# SCC.net
KiCad netlist of a schematic drawn in EAGLE
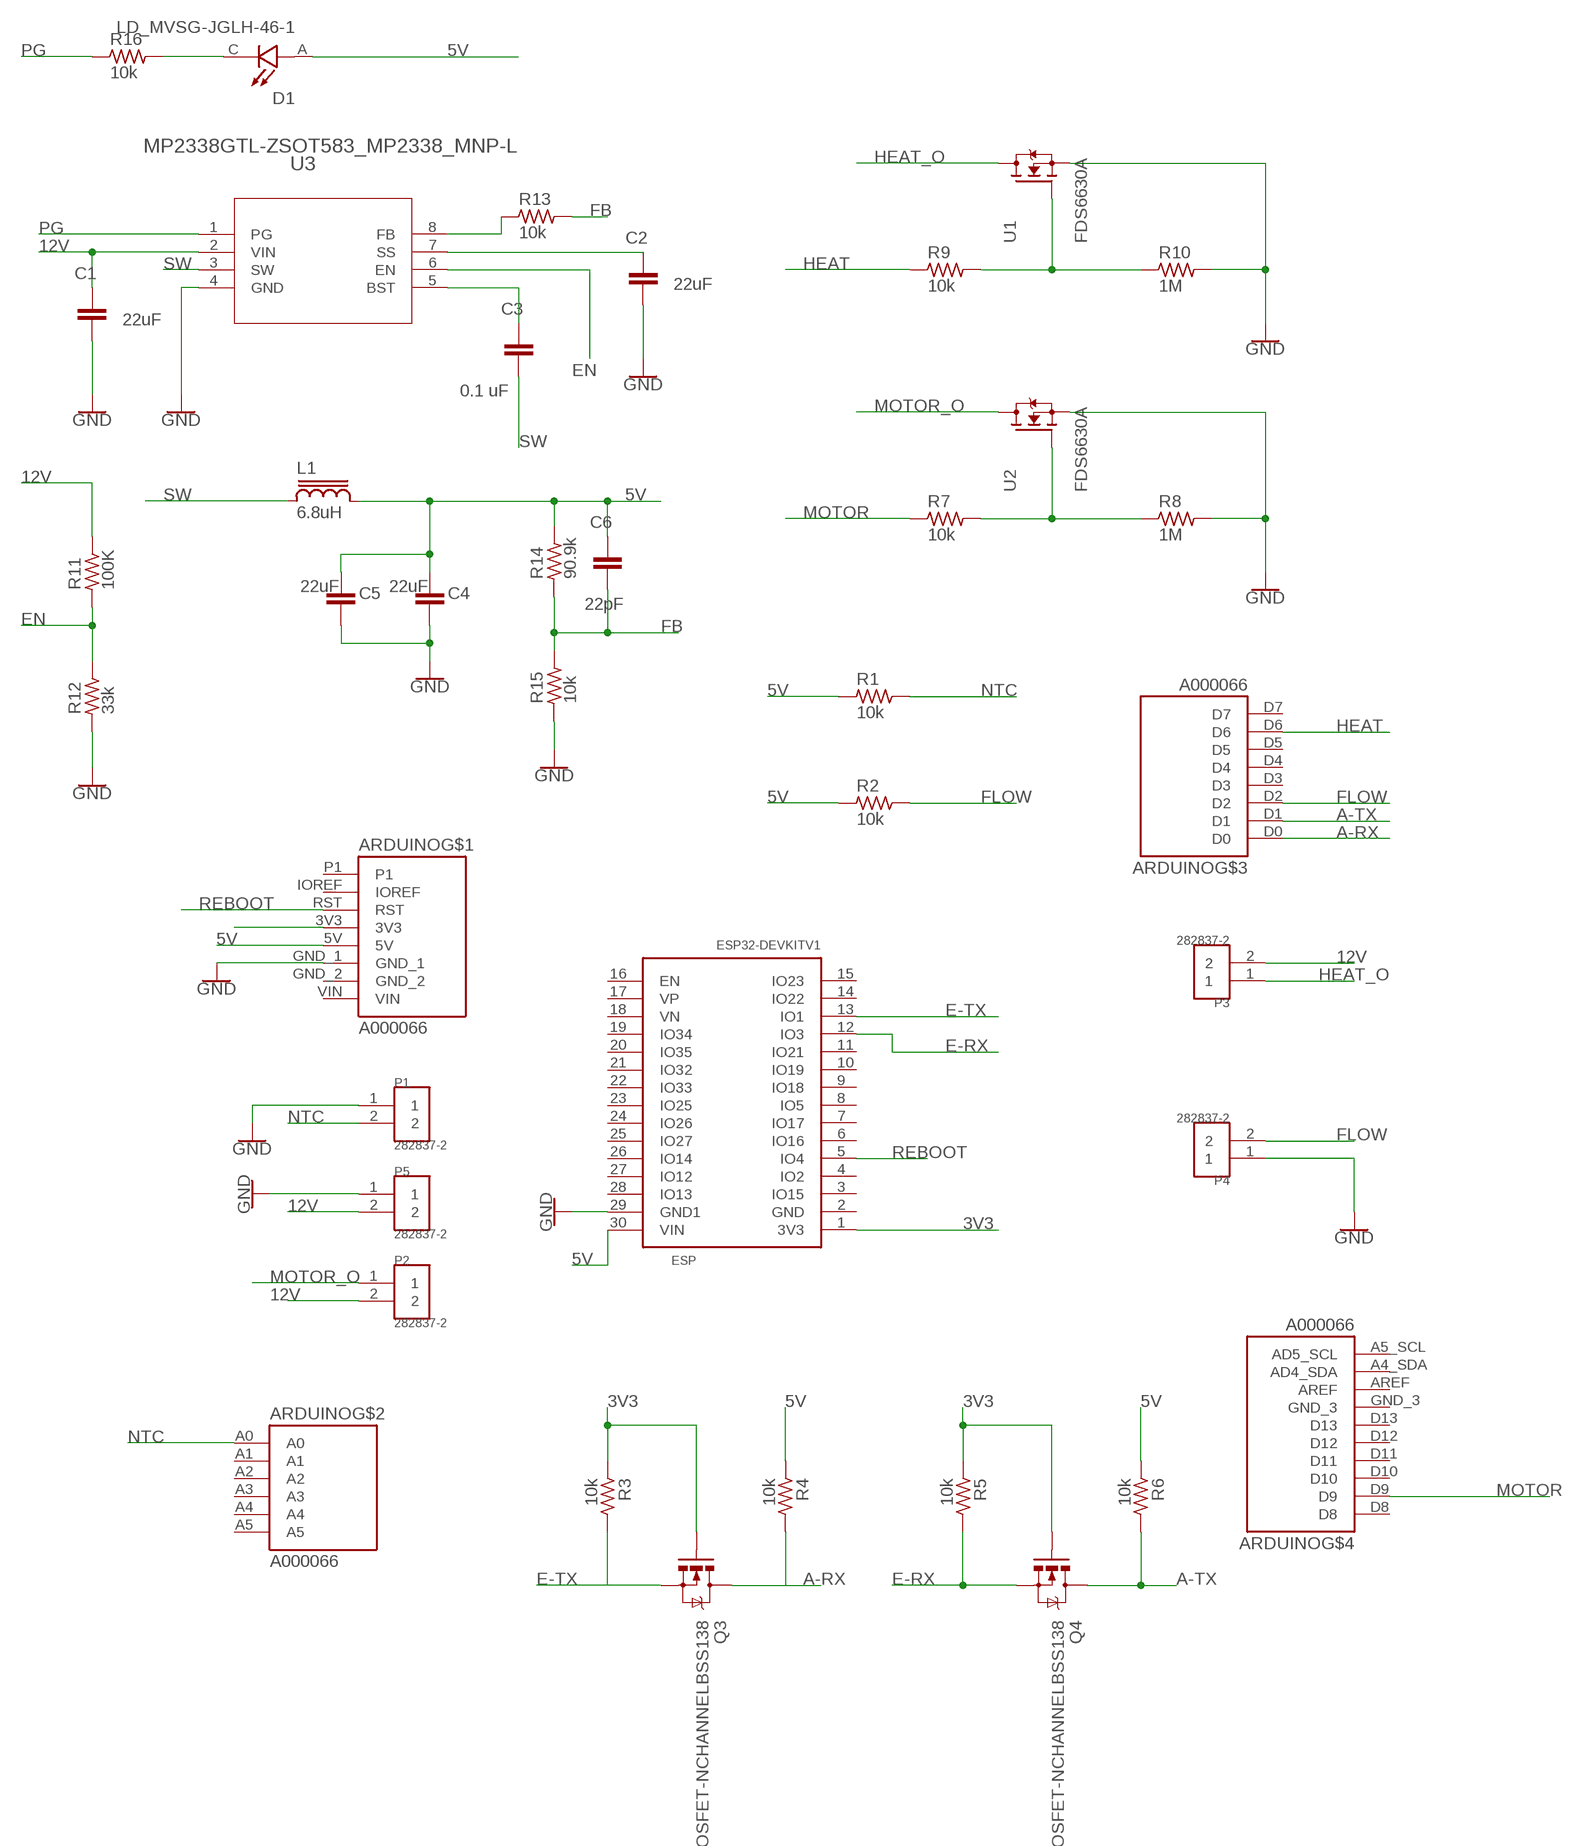
[diagram p0: schematic, sheet 1]

(export (version "E")
  (design (tool "Eeschema 10.0.6"))
  (components
    (comp (ref "ARDUINO")
      (value "A000066")
      (footprint "eagle-import:ARDUINO_A000066")
      (fields (field (name "MF") "Arduino"))
      (libsource (lib "eagle-import") (part "A000066"))
    )
    (comp (ref "C1")
      (value "22uF")
      (footprint "eagle-import:CAP_1206")
      (fields
        (field (name "DIGIKEY_PART_NUMBER") "GRM31CR60J107ME39L")
        (field (name "MANUFACTURER") "Murata Electronics North America")
        (field (name "CREATED_BY") "PCBLayout.com")
      )
      (libsource (lib "eagle-import") (part "GRM31CR60J107ME39L"))
    )
    (comp (ref "C2")
      (value "22uF")
      (footprint "eagle-import:CAP_1206")
      (fields
        (field (name "DIGIKEY_PART_NUMBER") "GRM31CR60J107ME39L")
        (field (name "MANUFACTURER") "Murata Electronics North America")
        (field (name "CREATED_BY") "PCBLayout.com")
      )
      (libsource (lib "eagle-import") (part "GRM31CR60J107ME39L"))
    )
    (comp (ref "C3")
      (value "0.1 uF")
      (footprint "eagle-import:CAP_0805")
      (fields
        (field (name "DIGIKEY_PART_NUMBER") "311-1140-2-ND")
        (field (name "MANUFACTURER") "Yageo")
        (field (name "MPN") "CC0805KRX7R9BB104")
        (field (name "CREATED_BY") "PCBLayout.com")
      )
      (libsource (lib "eagle-import") (part "CC0805KRX7R9BB104"))
    )
    (comp (ref "C4")
      (value "22uF")
      (footprint "eagle-import:CAP_1206")
      (fields
        (field (name "DIGIKEY_PART_NUMBER") "GRM31CR60J107ME39L")
        (field (name "MANUFACTURER") "Murata Electronics North America")
        (field (name "CREATED_BY") "PCBLayout.com")
      )
      (libsource (lib "eagle-import") (part "GRM31CR60J107ME39L"))
    )
    (comp (ref "C5")
      (value "22uF")
      (footprint "eagle-import:CAP_1206")
      (fields
        (field (name "DIGIKEY_PART_NUMBER") "GRM31CR60J107ME39L")
        (field (name "MANUFACTURER") "Murata Electronics North America")
        (field (name "CREATED_BY") "PCBLayout.com")
      )
      (libsource (lib "eagle-import") (part "GRM31CR60J107ME39L"))
    )
    (comp (ref "C6")
      (value "22pF")
      (footprint "eagle-import:CAP_0805")
      (fields
        (field (name "DIGIKEY_PART_NUMBER") "311-1140-2-ND")
        (field (name "MANUFACTURER") "Yageo")
        (field (name "MPN") "CC0805KRX7R9BB104")
        (field (name "CREATED_BY") "PCBLayout.com")
      )
      (libsource (lib "eagle-import") (part "CC0805KRX7R9BB104"))
    )
    (comp (ref "D1")
      (value "LD_MVSG-JGLH-46-1")
      (footprint "eagle-import:LED_LD_MVSG-JGLH-46-1")
      (fields (field (name "MF") "OSRAM Opto") (field (name "MP") "LCW MVSG.EC-AZBZ-4R9T-1"))
      (libsource (lib "eagle-import") (part "LD_MVSG-JGLH-46-1"))
    )
    (comp (ref "ESP")
      (value "ESP32DEVKITV1")
      (footprint "eagle-import:ESP32-DEVKITV1")
      (libsource (lib "eagle-import") (part "ESP32DEVKITV1"))
    )
    (comp (ref "L1")
      (value "6.8uH")
      (footprint "eagle-import:INDUCTOR-BOURNS_SRN8040")
      (libsource (lib "eagle-import") (part "INDUCTOR-BOURNS_SRN8040"))
    )
    (comp (ref "P1")
      (value "282837-2")
      (footprint "eagle-import:TE_282837-2")
      (fields (field (name "MF") "On Shore") (field (name "MP") "OSTTE020104"))
      (libsource (lib "eagle-import") (part "282837-2"))
    )
    (comp (ref "P2")
      (value "282837-2")
      (footprint "eagle-import:TE_282837-2")
      (fields (field (name "MF") "On Shore") (field (name "MP") "OSTTE020104"))
      (libsource (lib "eagle-import") (part "282837-2"))
    )
    (comp (ref "P3")
      (value "282837-2")
      (footprint "eagle-import:TE_282837-2")
      (fields (field (name "MF") "On Shore") (field (name "MP") "OSTTE020104"))
      (libsource (lib "eagle-import") (part "282837-2"))
    )
    (comp (ref "P4")
      (value "282837-2")
      (footprint "eagle-import:TE_282837-2")
      (fields (field (name "MF") "On Shore") (field (name "MP") "OSTTE020104"))
      (libsource (lib "eagle-import") (part "282837-2"))
    )
    (comp (ref "P5")
      (value "282837-2")
      (footprint "eagle-import:TE_282837-2")
      (fields (field (name "MF") "On Shore") (field (name "MP") "OSTTE020104"))
      (libsource (lib "eagle-import") (part "282837-2"))
    )
    (comp (ref "Q3")
      (value "MOSFET-NCHANNELBSS138")
      (footprint "eagle-import:SOT23")
      (libsource (lib "eagle-import") (part "MOSFET-NCHANNELBSS138"))
    )
    (comp (ref "Q4")
      (value "MOSFET-NCHANNELBSS138")
      (footprint "eagle-import:SOT23")
      (libsource (lib "eagle-import") (part "MOSFET-NCHANNELBSS138"))
    )
    (comp (ref "R1")
      (value "10k")
      (footprint "eagle-import:RC-MASTER-SMD_R0603MP")
      (libsource (lib "eagle-import") (part "RC-MASTER-SMD_R_0603MP"))
    )
    (comp (ref "R2")
      (value "10k")
      (footprint "eagle-import:RC-MASTER-SMD_R0603MP")
      (libsource (lib "eagle-import") (part "RC-MASTER-SMD_R_0603MP"))
    )
    (comp (ref "R3")
      (value "10k")
      (footprint "eagle-import:RC-MASTER-SMD_R0603MP")
      (libsource (lib "eagle-import") (part "RC-MASTER-SMD_R_0603MP"))
    )
    (comp (ref "R4")
      (value "10k")
      (footprint "eagle-import:RC-MASTER-SMD_R0603MP")
      (libsource (lib "eagle-import") (part "RC-MASTER-SMD_R_0603MP"))
    )
    (comp (ref "R5")
      (value "10k")
      (footprint "eagle-import:RC-MASTER-SMD_R0603MP")
      (libsource (lib "eagle-import") (part "RC-MASTER-SMD_R_0603MP"))
    )
    (comp (ref "R6")
      (value "10k")
      (footprint "eagle-import:RC-MASTER-SMD_R0603MP")
      (libsource (lib "eagle-import") (part "RC-MASTER-SMD_R_0603MP"))
    )
    (comp (ref "R7")
      (value "10k")
      (footprint "eagle-import:RC-MASTER-SMD_R0603MP")
      (libsource (lib "eagle-import") (part "RC-MASTER-SMD_R_0603MP"))
    )
    (comp (ref "R8")
      (value "1M")
      (footprint "eagle-import:RC-MASTER-SMD_R0603MP")
      (libsource (lib "eagle-import") (part "RC-MASTER-SMD_R_0603MP"))
    )
    (comp (ref "R9")
      (value "10k")
      (footprint "eagle-import:RC-MASTER-SMD_R0603MP")
      (libsource (lib "eagle-import") (part "RC-MASTER-SMD_R_0603MP"))
    )
    (comp (ref "R10")
      (value "1M")
      (footprint "eagle-import:RC-MASTER-SMD_R0603MP")
      (libsource (lib "eagle-import") (part "RC-MASTER-SMD_R_0603MP"))
    )
    (comp (ref "R11")
      (value "100K")
      (footprint "eagle-import:RC-MASTER-SMD_R0603MP")
      (libsource (lib "eagle-import") (part "RC-MASTER-SMD_R_0603MP"))
    )
    (comp (ref "R12")
      (value "33k")
      (footprint "eagle-import:RC-MASTER-SMD_R0603MP")
      (libsource (lib "eagle-import") (part "RC-MASTER-SMD_R_0603MP"))
    )
    (comp (ref "R13")
      (value "10k")
      (footprint "eagle-import:RC-MASTER-SMD_R0603MP")
      (libsource (lib "eagle-import") (part "RC-MASTER-SMD_R_0603MP"))
    )
    (comp (ref "R14")
      (value "90.9k")
      (footprint "eagle-import:RC-MASTER-SMD_R0603MP")
      (libsource (lib "eagle-import") (part "RC-MASTER-SMD_R_0603MP"))
    )
    (comp (ref "R15")
      (value "10k")
      (footprint "eagle-import:RC-MASTER-SMD_R0603MP")
      (libsource (lib "eagle-import") (part "RC-MASTER-SMD_R_0603MP"))
    )
    (comp (ref "R16")
      (value "10k")
      (footprint "eagle-import:RC-MASTER-SMD_R0603MP")
      (libsource (lib "eagle-import") (part "RC-MASTER-SMD_R_0603MP"))
    )
    (comp (ref "U1")
      (value "FDS6630A")
      (footprint "eagle-import:SOIC127P600X175-8N")
      (fields (field (name "MANUFACTURER") "ON SEMICONDUCTOR"))
      (libsource (lib "eagle-import") (part "FDS6630A"))
    )
    (comp (ref "U2")
      (value "FDS6630A")
      (footprint "eagle-import:SOIC127P600X175-8N")
      (fields (field (name "MANUFACTURER") "ON SEMICONDUCTOR"))
      (libsource (lib "eagle-import") (part "FDS6630A"))
    )
    (comp (ref "U3")
      (value "MP2338GTL-ZSOT583_MP2338_MNP-L")
      (footprint "eagle-import:SOT583_MP2338_MNP-L")
      (fields
        (field (name "MANUFACTURER_PART_NUMBER") "MP2338GTL-Z")
        (field (name "COPYRIGHT") "Copyright (C) 2026 Ultra Librarian. All rights reserved.")
      )
      (libsource (lib "eagle-import") (part "MP2338GTL-ZSOT583_MP2338_MNP-L"))
    )
  )
  (nets
    (net (code "1") (name "/3V3") (class "Default")
      (node (ref "ESP") (pin "1") (pinfunction "3V3_1") (pintype "bidirectional"))
      (node (ref "Q3") (pin "1") (pinfunction "G_1") (pintype "passive"))
      (node (ref "Q4") (pin "1") (pinfunction "G_1") (pintype "passive"))
      (node (ref "R3") (pin "1") (pinfunction "1_1") (pintype "passive"))
      (node (ref "R5") (pin "1") (pinfunction "1_1") (pintype "passive"))
    )
    (net (code "2") (name "/5V") (class "Default")
      (node (ref "ARDUINO") (pin "5V") (pinfunction "5V_5V") (pintype "power_in"))
      (node (ref "C4") (pin "1") (pinfunction "1_1") (pintype "passive"))
      (node (ref "C5") (pin "1") (pinfunction "1_1") (pintype "passive"))
      (node (ref "C6") (pin "1") (pinfunction "1_1") (pintype "passive"))
      (node (ref "D1") (pin "A") (pinfunction "A_A") (pintype "passive"))
      (node (ref "ESP") (pin "30") (pinfunction "VIN_30") (pintype "bidirectional"))
      (node (ref "L1") (pin "2") (pinfunction "2_2") (pintype "passive"))
      (node (ref "R1") (pin "1") (pinfunction "1_1") (pintype "passive"))
      (node (ref "R14") (pin "2") (pinfunction "2_2") (pintype "passive"))
      (node (ref "R2") (pin "1") (pinfunction "1_1") (pintype "passive"))
      (node (ref "R4") (pin "1") (pinfunction "1_1") (pintype "passive"))
      (node (ref "R6") (pin "1") (pinfunction "1_1") (pintype "passive"))
    )
    (net (code "3") (name "/12V") (class "Default")
      (node (ref "C1") (pin "1") (pinfunction "1_1") (pintype "passive"))
      (node (ref "P2") (pin "2") (pinfunction "2_2") (pintype "passive"))
      (node (ref "P3") (pin "2") (pinfunction "2_2") (pintype "passive"))
      (node (ref "P5") (pin "2") (pinfunction "2_2") (pintype "passive"))
      (node (ref "R11") (pin "2") (pinfunction "2_2") (pintype "passive"))
      (node (ref "U3") (pin "2") (pinfunction "VIN_2") (pintype "power_in"))
    )
    (net (code "4") (name "/A-RX") (class "Default")
      (node (ref "ARDUINO") (pin "D0") (pinfunction "D0_D0") (pintype "bidirectional"))
      (node (ref "Q3") (pin "3") (pinfunction "D_3") (pintype "passive"))
      (node (ref "R4") (pin "2") (pinfunction "2_2") (pintype "passive"))
    )
    (net (code "5") (name "/A-TX") (class "Default")
      (node (ref "ARDUINO") (pin "D1") (pinfunction "D1_D1") (pintype "bidirectional"))
      (node (ref "Q4") (pin "3") (pinfunction "D_3") (pintype "passive"))
      (node (ref "R6") (pin "2") (pinfunction "2_2") (pintype "passive"))
    )
    (net (code "6") (name "/E-RX") (class "Default")
      (node (ref "ESP") (pin "12") (pinfunction "IO3_12") (pintype "bidirectional"))
      (node (ref "Q4") (pin "2") (pinfunction "S_2") (pintype "passive"))
      (node (ref "R5") (pin "2") (pinfunction "2_2") (pintype "passive"))
    )
    (net (code "7") (name "/E-TX") (class "Default")
      (node (ref "ESP") (pin "13") (pinfunction "IO1_13") (pintype "bidirectional"))
      (node (ref "Q3") (pin "2") (pinfunction "S_2") (pintype "passive"))
      (node (ref "R3") (pin "2") (pinfunction "2_2") (pintype "passive"))
    )
    (net (code "8") (name "/EN") (class "Default")
      (node (ref "R11") (pin "1") (pinfunction "1_1") (pintype "passive"))
      (node (ref "R12") (pin "2") (pinfunction "2_2") (pintype "passive"))
      (node (ref "U3") (pin "6") (pinfunction "EN_6") (pintype "input"))
    )
    (net (code "9") (name "/FB") (class "Default")
      (node (ref "C6") (pin "2") (pinfunction "2_2") (pintype "passive"))
      (node (ref "R13") (pin "2") (pinfunction "2_2") (pintype "passive"))
      (node (ref "R14") (pin "1") (pinfunction "1_1") (pintype "passive"))
      (node (ref "R15") (pin "2") (pinfunction "2_2") (pintype "passive"))
    )
    (net (code "10") (name "/FLOW") (class "Default")
      (node (ref "ARDUINO") (pin "D2") (pinfunction "D2_D2") (pintype "bidirectional"))
      (node (ref "P4") (pin "2") (pinfunction "2_2") (pintype "passive"))
      (node (ref "R2") (pin "2") (pinfunction "2_2") (pintype "passive"))
    )
    (net (code "11") (name "/GND_2") (class "Default")
      (node (ref "ARDUINO") (pin "GND_2") (pinfunction "GND_2_GND_2") (pintype "power_in"))
    )
    (net (code "12") (name "/GND_3") (class "Default")
      (node (ref "ARDUINO") (pin "GND_3") (pinfunction "GND_3_GND_3") (pintype "power_in"))
    )
    (net (code "13") (name "/HEAT") (class "Default")
      (node (ref "ARDUINO") (pin "D6") (pinfunction "D6_D6") (pintype "bidirectional"))
      (node (ref "R9") (pin "1") (pinfunction "1_1") (pintype "passive"))
    )
    (net (code "14") (name "/HEAT_O") (class "Default")
      (node (ref "P3") (pin "1") (pinfunction "1_1") (pintype "passive"))
      (node (ref "U1") (pin "5") (pinfunction "D_5") (pintype "passive"))
      (node (ref "U1") (pin "6") (pinfunction "D_6") (pintype "passive"))
      (node (ref "U1") (pin "7") (pinfunction "D_7") (pintype "passive"))
      (node (ref "U1") (pin "8") (pinfunction "D_8") (pintype "passive"))
    )
    (net (code "15") (name "/MOTOR") (class "Default")
      (node (ref "ARDUINO") (pin "D9") (pinfunction "D9_D9") (pintype "bidirectional"))
      (node (ref "R7") (pin "1") (pinfunction "1_1") (pintype "passive"))
    )
    (net (code "16") (name "/MOTOR_O") (class "Default")
      (node (ref "P2") (pin "1") (pinfunction "1_1") (pintype "passive"))
      (node (ref "U2") (pin "5") (pinfunction "D_5") (pintype "passive"))
      (node (ref "U2") (pin "6") (pinfunction "D_6") (pintype "passive"))
      (node (ref "U2") (pin "7") (pinfunction "D_7") (pintype "passive"))
      (node (ref "U2") (pin "8") (pinfunction "D_8") (pintype "passive"))
    )
    (net (code "17") (name "/NTC") (class "Default")
      (node (ref "ARDUINO") (pin "A0") (pinfunction "A0_A0") (pintype "bidirectional"))
      (node (ref "P1") (pin "2") (pinfunction "2_2") (pintype "passive"))
      (node (ref "R1") (pin "2") (pinfunction "2_2") (pintype "passive"))
    )
    (net (code "18") (name "/PG") (class "Default")
      (node (ref "R16") (pin "1") (pinfunction "1_1") (pintype "passive"))
      (node (ref "U3") (pin "1") (pinfunction "PG_1") (pintype "output"))
    )
    (net (code "19") (name "/REBOOT") (class "Default")
      (node (ref "ARDUINO") (pin "RST") (pinfunction "RST_RST") (pintype "bidirectional"))
      (node (ref "ESP") (pin "5") (pinfunction "IO4_5") (pintype "bidirectional"))
    )
    (net (code "20") (name "/SW") (class "Default")
      (node (ref "C3") (pin "2") (pinfunction "2_2") (pintype "passive"))
      (node (ref "L1") (pin "1") (pinfunction "1_1") (pintype "passive"))
      (node (ref "U3") (pin "3") (pinfunction "SW_3") (pintype "output"))
    )
    (net (code "21") (name "/VIN") (class "Default")
      (node (ref "ARDUINO") (pin "VIN") (pinfunction "VIN_VIN") (pintype "power_in"))
    )
    (net (code "22") (name "GND") (class "Default")
      (node (ref "ARDUINO") (pin "GND_1") (pinfunction "GND_1_GND_1") (pintype "power_in"))
      (node (ref "C1") (pin "2") (pinfunction "2_2") (pintype "passive"))
      (node (ref "C2") (pin "2") (pinfunction "2_2") (pintype "passive"))
      (node (ref "C4") (pin "2") (pinfunction "2_2") (pintype "passive"))
      (node (ref "C5") (pin "2") (pinfunction "2_2") (pintype "passive"))
      (node (ref "ESP") (pin "29") (pinfunction "GND1_29") (pintype "bidirectional"))
      (node (ref "P1") (pin "1") (pinfunction "1_1") (pintype "passive"))
      (node (ref "P4") (pin "1") (pinfunction "1_1") (pintype "passive"))
      (node (ref "P5") (pin "1") (pinfunction "1_1") (pintype "passive"))
      (node (ref "R10") (pin "2") (pinfunction "2_2") (pintype "passive"))
      (node (ref "R12") (pin "1") (pinfunction "1_1") (pintype "passive"))
      (node (ref "R15") (pin "1") (pinfunction "1_1") (pintype "passive"))
      (node (ref "R8") (pin "2") (pinfunction "2_2") (pintype "passive"))
      (node (ref "U1") (pin "1") (pinfunction "S_1") (pintype "passive"))
      (node (ref "U1") (pin "2") (pinfunction "S_2") (pintype "passive"))
      (node (ref "U1") (pin "3") (pinfunction "S_3") (pintype "passive"))
      (node (ref "U2") (pin "1") (pinfunction "S_1") (pintype "passive"))
      (node (ref "U2") (pin "2") (pinfunction "S_2") (pintype "passive"))
      (node (ref "U2") (pin "3") (pinfunction "S_3") (pintype "passive"))
      (node (ref "U3") (pin "4") (pinfunction "GND_4") (pintype "power_in"))
    )
    (net (code "23") (name "Net-(D1-PadC)") (class "Default")
      (node (ref "D1") (pin "C") (pinfunction "C_C") (pintype "passive"))
      (node (ref "R16") (pin "2") (pinfunction "2_2") (pintype "passive"))
    )
    (net (code "24") (name "Net-(U1-G)") (class "Default")
      (node (ref "R10") (pin "1") (pinfunction "1_1") (pintype "passive"))
      (node (ref "R9") (pin "2") (pinfunction "2_2") (pintype "passive"))
      (node (ref "U1") (pin "4") (pinfunction "G_4") (pintype "passive"))
    )
    (net (code "25") (name "Net-(U2-G)") (class "Default")
      (node (ref "R7") (pin "2") (pinfunction "2_2") (pintype "passive"))
      (node (ref "R8") (pin "1") (pinfunction "1_1") (pintype "passive"))
      (node (ref "U2") (pin "4") (pinfunction "G_4") (pintype "passive"))
    )
    (net (code "26") (name "Net-(U3-BST)") (class "Default")
      (node (ref "C3") (pin "1") (pinfunction "1_1") (pintype "passive"))
      (node (ref "U3") (pin "5") (pinfunction "BST_5") (pintype "power_in"))
    )
    (net (code "27") (name "Net-(U3-FB)") (class "Default")
      (node (ref "R13") (pin "1") (pinfunction "1_1") (pintype "passive"))
      (node (ref "U3") (pin "8") (pinfunction "FB_8") (pintype "output"))
    )
    (net (code "28") (name "Net-(U3-SS)") (class "Default")
      (node (ref "C2") (pin "1") (pinfunction "1_1") (pintype "passive"))
      (node (ref "U3") (pin "7") (pinfunction "SS_7") (pintype "passive"))
    )
    (net (code "29") (name "unconnected-(ARDUINO-Pad3V3)") (class "Default")
      (node (ref "ARDUINO") (pin "3V3") (pinfunction "3V3_3V3") (pintype "power_in"))
    )
    (net (code "30") (name "unconnected-(ARDUINO-PadA1)") (class "Default")
      (node (ref "ARDUINO") (pin "A1") (pinfunction "A1_A1") (pintype "bidirectional"))
    )
    (net (code "31") (name "unconnected-(ARDUINO-PadA2)") (class "Default")
      (node (ref "ARDUINO") (pin "A2") (pinfunction "A2_A2") (pintype "bidirectional"))
    )
    (net (code "32") (name "unconnected-(ARDUINO-PadA3)") (class "Default")
      (node (ref "ARDUINO") (pin "A3") (pinfunction "A3_A3") (pintype "bidirectional"))
    )
    (net (code "33") (name "unconnected-(ARDUINO-PadA4)") (class "Default")
      (node (ref "ARDUINO") (pin "A4") (pinfunction "A4_A4") (pintype "bidirectional"))
    )
    (net (code "34") (name "unconnected-(ARDUINO-PadA5)") (class "Default")
      (node (ref "ARDUINO") (pin "A5") (pinfunction "A5_A5") (pintype "bidirectional"))
    )
    (net (code "35") (name "unconnected-(ARDUINO-PadAREF)") (class "Default")
      (node (ref "ARDUINO") (pin "AREF") (pinfunction "AREF_AREF") (pintype "bidirectional"))
    )
    (net (code "36") (name "unconnected-(ARDUINO-PadD3)") (class "Default")
      (node (ref "ARDUINO") (pin "D3") (pinfunction "D3_D3") (pintype "bidirectional"))
    )
    (net (code "37") (name "unconnected-(ARDUINO-PadD4)") (class "Default")
      (node (ref "ARDUINO") (pin "D4") (pinfunction "D4_D4") (pintype "bidirectional"))
    )
    (net (code "38") (name "unconnected-(ARDUINO-PadD5)") (class "Default")
      (node (ref "ARDUINO") (pin "D5") (pinfunction "D5_D5") (pintype "bidirectional"))
    )
    (net (code "39") (name "unconnected-(ARDUINO-PadD7)") (class "Default")
      (node (ref "ARDUINO") (pin "D7") (pinfunction "D7_D7") (pintype "bidirectional"))
    )
    (net (code "40") (name "unconnected-(ARDUINO-PadD8)") (class "Default")
      (node (ref "ARDUINO") (pin "D8") (pinfunction "D8_D8") (pintype "bidirectional"))
    )
    (net (code "41") (name "unconnected-(ARDUINO-PadD10)") (class "Default")
      (node (ref "ARDUINO") (pin "D10") (pinfunction "D10_D10") (pintype "bidirectional"))
    )
    (net (code "42") (name "unconnected-(ARDUINO-PadD11)") (class "Default")
      (node (ref "ARDUINO") (pin "D11") (pinfunction "D11_D11") (pintype "bidirectional"))
    )
    (net (code "43") (name "unconnected-(ARDUINO-PadD12)") (class "Default")
      (node (ref "ARDUINO") (pin "D12") (pinfunction "D12_D12") (pintype "bidirectional"))
    )
    (net (code "44") (name "unconnected-(ARDUINO-PadD13)") (class "Default")
      (node (ref "ARDUINO") (pin "D13") (pinfunction "D13_D13") (pintype "bidirectional"))
    )
    (net (code "45") (name "unconnected-(ARDUINO-PadIOREF)") (class "Default")
      (node (ref "ARDUINO") (pin "IOREF") (pinfunction "IOREF_IOREF") (pintype "bidirectional"))
    )
    (net (code "46") (name "unconnected-(ARDUINO-PadP1)") (class "Default")
      (node (ref "ARDUINO") (pin "P1") (pinfunction "P1_P1") (pintype "bidirectional"))
    )
    (net (code "47") (name "unconnected-(ARDUINOD-AD4_SDA-PadA4_SDA)") (class "Default")
      (node (ref "ARDUINO") (pin "A4_SDA") (pinfunction "AD4_SDA_A4_SDA") (pintype "bidirectional"))
    )
    (net (code "48") (name "unconnected-(ARDUINOD-AD5_SCL-PadA5_SCL)") (class "Default")
      (node (ref "ARDUINO") (pin "A5_SCL") (pinfunction "AD5_SCL_A5_SCL") (pintype "bidirectional"))
    )
    (net (code "49") (name "unconnected-(ESP-EN-Pad16)") (class "Default")
      (node (ref "ESP") (pin "16") (pinfunction "EN_16") (pintype "bidirectional"))
    )
    (net (code "50") (name "unconnected-(ESP-GND-Pad2)") (class "Default")
      (node (ref "ESP") (pin "2") (pinfunction "GND_2") (pintype "bidirectional"))
    )
    (net (code "51") (name "unconnected-(ESP-IO2-Pad4)") (class "Default")
      (node (ref "ESP") (pin "4") (pinfunction "IO2_4") (pintype "bidirectional"))
    )
    (net (code "52") (name "unconnected-(ESP-IO5-Pad8)") (class "Default")
      (node (ref "ESP") (pin "8") (pinfunction "IO5_8") (pintype "bidirectional"))
    )
    (net (code "53") (name "unconnected-(ESP-IO12-Pad27)") (class "Default")
      (node (ref "ESP") (pin "27") (pinfunction "IO12_27") (pintype "bidirectional"))
    )
    (net (code "54") (name "unconnected-(ESP-IO13-Pad28)") (class "Default")
      (node (ref "ESP") (pin "28") (pinfunction "IO13_28") (pintype "bidirectional"))
    )
    (net (code "55") (name "unconnected-(ESP-IO14-Pad26)") (class "Default")
      (node (ref "ESP") (pin "26") (pinfunction "IO14_26") (pintype "bidirectional"))
    )
    (net (code "56") (name "unconnected-(ESP-IO15-Pad3)") (class "Default")
      (node (ref "ESP") (pin "3") (pinfunction "IO15_3") (pintype "bidirectional"))
    )
    (net (code "57") (name "unconnected-(ESP-IO16-Pad6)") (class "Default")
      (node (ref "ESP") (pin "6") (pinfunction "IO16_6") (pintype "bidirectional"))
    )
    (net (code "58") (name "unconnected-(ESP-IO17-Pad7)") (class "Default")
      (node (ref "ESP") (pin "7") (pinfunction "IO17_7") (pintype "bidirectional"))
    )
    (net (code "59") (name "unconnected-(ESP-IO18-Pad9)") (class "Default")
      (node (ref "ESP") (pin "9") (pinfunction "IO18_9") (pintype "bidirectional"))
    )
    (net (code "60") (name "unconnected-(ESP-IO19-Pad10)") (class "Default")
      (node (ref "ESP") (pin "10") (pinfunction "IO19_10") (pintype "bidirectional"))
    )
    (net (code "61") (name "unconnected-(ESP-IO21-Pad11)") (class "Default")
      (node (ref "ESP") (pin "11") (pinfunction "IO21_11") (pintype "bidirectional"))
    )
    (net (code "62") (name "unconnected-(ESP-IO22-Pad14)") (class "Default")
      (node (ref "ESP") (pin "14") (pinfunction "IO22_14") (pintype "bidirectional"))
    )
    (net (code "63") (name "unconnected-(ESP-IO23-Pad15)") (class "Default")
      (node (ref "ESP") (pin "15") (pinfunction "IO23_15") (pintype "bidirectional"))
    )
    (net (code "64") (name "unconnected-(ESP-IO25-Pad23)") (class "Default")
      (node (ref "ESP") (pin "23") (pinfunction "IO25_23") (pintype "bidirectional"))
    )
    (net (code "65") (name "unconnected-(ESP-IO26-Pad24)") (class "Default")
      (node (ref "ESP") (pin "24") (pinfunction "IO26_24") (pintype "bidirectional"))
    )
    (net (code "66") (name "unconnected-(ESP-IO27-Pad25)") (class "Default")
      (node (ref "ESP") (pin "25") (pinfunction "IO27_25") (pintype "bidirectional"))
    )
    (net (code "67") (name "unconnected-(ESP-IO32-Pad21)") (class "Default")
      (node (ref "ESP") (pin "21") (pinfunction "IO32_21") (pintype "bidirectional"))
    )
    (net (code "68") (name "unconnected-(ESP-IO33-Pad22)") (class "Default")
      (node (ref "ESP") (pin "22") (pinfunction "IO33_22") (pintype "bidirectional"))
    )
    (net (code "69") (name "unconnected-(ESP-IO34-Pad19)") (class "Default")
      (node (ref "ESP") (pin "19") (pinfunction "IO34_19") (pintype "bidirectional"))
    )
    (net (code "70") (name "unconnected-(ESP-IO35-Pad20)") (class "Default")
      (node (ref "ESP") (pin "20") (pinfunction "IO35_20") (pintype "bidirectional"))
    )
    (net (code "71") (name "unconnected-(ESP-VN-Pad18)") (class "Default")
      (node (ref "ESP") (pin "18") (pinfunction "VN_18") (pintype "bidirectional"))
    )
    (net (code "72") (name "unconnected-(ESP-VP-Pad17)") (class "Default")
      (node (ref "ESP") (pin "17") (pinfunction "VP_17") (pintype "bidirectional"))
    )
  )
)
